# Peripherals.net
KiCad netlist of a schematic drawn in Altium Designer
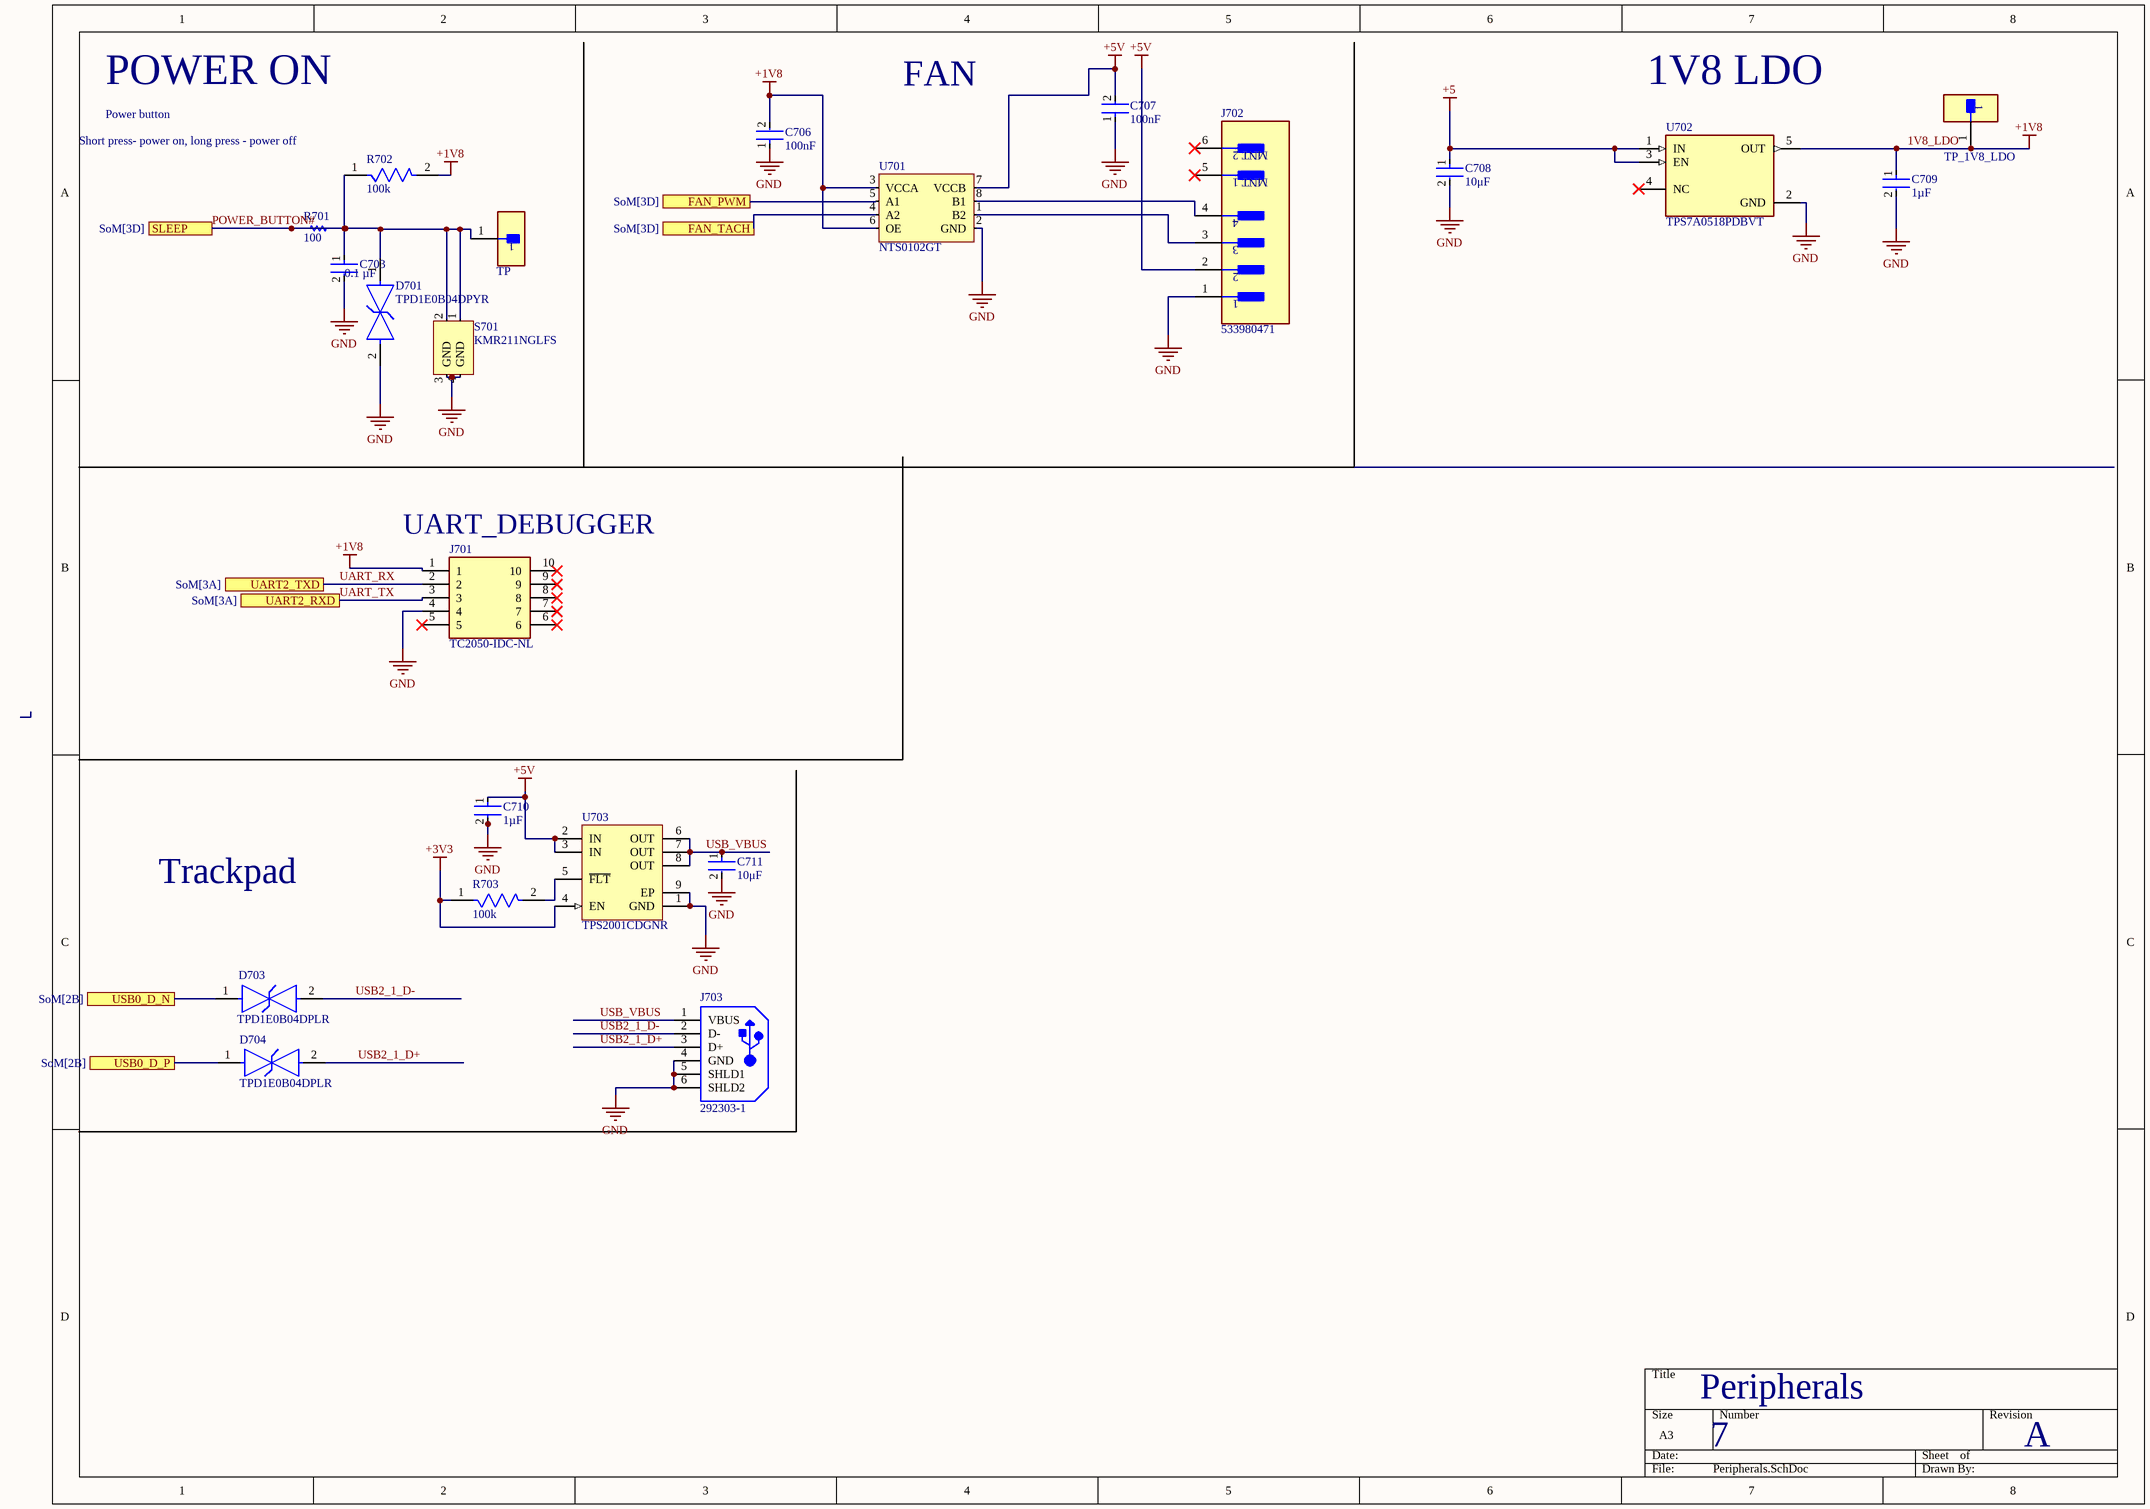
[diagram p0: Peripherals.SchDoc]

(export (version "E")
  (design (tool "Eeschema 10.0.6"))
  (components
    (comp (ref "C703")
      (value "0.1 µF")
      (footprint "FP-GRM155-0_05-IPC_B")
      (description "Chip Multilayer Ceramic Capacitors for General Purpose, 0402, 0.10uF, X7R, 15%, 10%, 50V")
      (fields (field (name "TOLERANCE") "10%"))
      (libsource (lib "Altium Content Vault") (part "02cd4be3c70576c341d710602a673aa"))
    )
    (comp (ref "C706")
      (value "100nF")
      (footprint "FP-GRM155-0_05-IPC_B")
      (description "Chip Multilayer Ceramic Capacitors for General Purpose, 0402, 0.10uF, X7R, 15%, 10%, 50V")
      (fields (field (name "VOLTAGE") "50V") (field (name "TOLERANCE") "10%"))
      (libsource (lib "Altium Content Vault") (part "02cd4be3c70576c341d710602a673aa"))
    )
    (comp (ref "C707")
      (value "100nF")
      (footprint "FP-GRM155-0_05-IPC_B")
      (description "Chip Multilayer Ceramic Capacitors for General Purpose, 0402, 0.10uF, X7R, 15%, 10%, 50V")
      (fields (field (name "VOLTAGE") "50V") (field (name "TOLERANCE") "10%"))
      (libsource (lib "Altium Content Vault") (part "02cd4be3c70576c341d710602a673aa"))
    )
    (comp (ref "C708")
      (value "10μF")
      (footprint "FP-GRM31C-0_2-e0_3_0_8-MFG")
      (description "Chip Multilayer Ceramic Capacitors for General Purpose, 1206, 10uF, X7R, 15%, 10%, 25V")
      (fields (field (name "TOLERANCE") "10%") (field (name "VOLTAGE") "25V"))
      (libsource (lib "Altium Content Vault") (part "02cd4be3c70576c341d710602a673aa"))
    )
    (comp (ref "C709")
      (value "1µF")
      (footprint "FP-GRM15-0_1-MFG")
      (description "CAP CER 1UF 10V X5R 0402")
      (fields
        (field (name "OCTOPART") "https://octopart.com/grm155r61a105ke15d-murata-197442")
        (field (name "MANUFACTURER PART NUMBER") "GRM155R61A105KE15D")
      )
      (libsource (lib "Altium Content Vault") (part "02cd4be3c70576c341d710602a673aa"))
    )
    (comp (ref "C710")
      (value "1µF")
      (footprint "FP-GRM15-0_1-MFG")
      (description "CAP CER 1UF 10V X5R 0402")
      (fields
        (field (name "OCTOPART") "https://octopart.com/grm155r61a105ke15d-murata-197442")
        (field (name "MANUFACTURER PART NUMBER") "GRM155R61A105KE15D")
      )
      (libsource (lib "Altium Content Vault") (part "02cd4be3c70576c341d710602a673aa"))
    )
    (comp (ref "C711")
      (value "10μF")
      (footprint "FP-GRM31C-0_2-e0_3_0_8-MFG")
      (description "Chip Multilayer Ceramic Capacitors for General Purpose, 1206, 10uF, X7R, 15%, 10%, 25V")
      (fields (field (name "TOLERANCE") "10%") (field (name "VOLTAGE") "25V"))
      (libsource (lib "Altium Content Vault") (part "02cd4be3c70576c341d710602a673aa"))
    )
    (comp (ref "D701")
      (value "TPD1E0B04DPYR")
      (footprint "FP-DPY0002A-MFG")
      (description "TVS DIODE 3.6V 19V 2X1SON")
      (libsource (lib "Altium Content Vault") (part "a36d0a7f8073cfe218e18526ba77789"))
    )
    (comp (ref "D703")
      (value "TPD1E0B04DPLR")
      (footprint "FP-DPL0002A-MFG")
      (description "TVS DIODE 3.6V 10.1V 2X2SON")
      (libsource (lib "Altium Content Vault") (part "a36d0a7f8073cfe218e18526ba77789"))
    )
    (comp (ref "D704")
      (value "TPD1E0B04DPLR")
      (footprint "FP-DPL0002A-MFG")
      (description "TVS DIODE 3.6V 10.1V 2X2SON")
      (libsource (lib "Altium Content Vault") (part "a36d0a7f8073cfe218e18526ba77789"))
    )
    (comp (ref "J701")
      (value "TC2050-IDC-NL")
      (footprint "TAG-CONNECT_TC2050-IDC-NL")
      (description "Adapter Cbl Plug Of Nails 10PIN")
      (libsource (lib "Evan") (part "TC2050-IDC-NL"))
    )
    (comp (ref "J702")
      (value "533980471")
      (footprint "FP-533980471-MFG")
      (description "CONN HEADER SMD 4POS 1.25MM")
      (fields
        (field (name "OCTOPART") "https://octopart.com/53398-0471-molex-655296")
        (field (name "MANUFACTURER") "Molex")
      )
      (libsource (lib "Altium Content Vault") (part "3b6f738a5616415d78381ad43816e4a"))
    )
    (comp (ref "J703")
      (value "292303-1")
      (footprint "TE-292303-1_V")
      (fields (field (name "MANUFACTURER") "TE Connectivity"))
      (libsource (lib "Altium Content Vault") (part "USB-4-2SHLD"))
    )
    (comp (ref "R701")
      (value "100")
      (footprint "RESC1005X40X25ML05T10")
      (fields (field (name "PART NUMBER") "RC0402FR-07100RL") (field (name "MANUFACTURER") "Yageo / Phycomp"))
      (libsource (lib "Altium Content Vault") (part "RES"))
    )
    (comp (ref "R702")
      (value "100k")
      (footprint "FP-RC0402-0_4-IPC_A")
      (description "RES 100K OHM 5% 1/16W 0402")
      (fields (field (name "TOLERANCE") "5%"))
      (libsource (lib "Altium Content Vault") (part "1029c3af85768c4190bb7ad29bc67b5"))
    )
    (comp (ref "R703")
      (value "100k")
      (footprint "FP-RC0402-0_4-IPC_A")
      (description "RES 100K OHM 5% 1/16W 0402")
      (fields (field (name "TOLERANCE") "5%"))
      (libsource (lib "Altium Content Vault") (part "1029c3af85768c4190bb7ad29bc67b5"))
    )
    (comp (ref "S701")
      (value "KMR211NGLFS")
      (footprint "SW_KMR211NGLFS")
      (description "Switch Tactile N.O. SPST Round Button Gull Wing 0.05A 32VDC 1VA 200000Cycle 1.2N SMD T/R")
      (libsource (lib "Evan") (part "KMR211NGLFS-Symbol-1"))
    )
    (comp (ref "TP700")
      (value "TP")
      (footprint "FP-S2751-46R-MFG")
      (description "PC TEST POINT NATURAL")
      (libsource (lib "") (part "dd45045ce8184df9e99e12baf3f412c_1"))
    )
    (comp (ref "TP701")
      (value "TP_1V8_LDO")
      (footprint "FP-S2751-46R-MFG")
      (description "PC TEST POINT NATURAL")
      (libsource (lib "Altium Content Vault") (part "dd45045ce8184df9e99e12baf3f412c"))
    )
    (comp (ref "U701")
      (value "NTS0102GT")
      (footprint "PSON50P100X195X50-8N")
      (description "Line Transceiver, PDSO8, 1 X 1.95 Mm, 0.50 Mm Height, Plastic, MO-252, SOT833-1, SON-8")
      (libsource (lib "Evan") (part "NTS0102GT-Symbol-1"))
    )
    (comp (ref "U702")
      (value "TPS7A0518PDBVT")
      (footprint "SOT95P280X145-5N")
      (description "200mA, ultra-low-IQ, high-accuracy, low-dropout voltage regulator with enable 5-SOT-23 -40 to 125")
      (libsource (lib "Evan") (part "TPS7A0518PDBVT"))
    )
    (comp (ref "U703")
      (value "TPS2001CDGNR")
      (footprint "DGN0008D_L")
      (fields (field (name "MANUFACTURER") "Texas Instruments"))
      (libsource (lib "Altium Content Vault") (part "TI-TPS2001CDGN8"))
    )
  )
  (nets
    (net (code "1") (name "+1V8") (class "Default")
      (node (ref "C706") (pin "2") (pinfunction "2_2") (pintype "passive"))
      (node (ref "C709") (pin "1") (pinfunction "1_1") (pintype "passive"))
      (node (ref "J701") (pin "1") (pinfunction "1_1") (pintype "passive"))
      (node (ref "R702") (pin "2") (pinfunction "2_2") (pintype "passive"))
      (node (ref "TP701") (pin "1") (pinfunction "1_1") (pintype "passive"))
      (node (ref "U701") (pin "3") (pinfunction "VCCA_3") (pintype "input"))
      (node (ref "U701") (pin "6") (pinfunction "OE_6") (pintype "input"))
      (node (ref "U702") (pin "5") (pinfunction "OUT_5") (pintype "output"))
    )
    (net (code "2") (name "+3V3") (class "Default")
      (node (ref "R703") (pin "1") (pinfunction "1_1") (pintype "passive"))
      (node (ref "U703") (pin "4") (pinfunction "EN_4") (pintype "input"))
    )
    (net (code "3") (name "+5") (class "Default")
      (node (ref "C708") (pin "1") (pinfunction "1_1") (pintype "passive"))
      (node (ref "U702") (pin "1") (pinfunction "IN_1") (pintype "input"))
      (node (ref "U702") (pin "3") (pinfunction "EN_3") (pintype "input"))
    )
    (net (code "4") (name "+5V") (class "Default")
      (node (ref "C707") (pin "2") (pinfunction "2_2") (pintype "passive"))
      (node (ref "C710") (pin "1") (pinfunction "1_1") (pintype "passive"))
      (node (ref "J702") (pin "2") (pinfunction "2_2") (pintype "passive"))
      (node (ref "U701") (pin "7") (pinfunction "VCCB_7") (pintype "input"))
      (node (ref "U703") (pin "2") (pinfunction "IN_2") (pintype "power_in"))
      (node (ref "U703") (pin "3") (pinfunction "IN_3") (pintype "power_in"))
    )
    (net (code "5") (name "/FAN_PWM") (class "Default")
      (node (ref "U701") (pin "5") (pinfunction "A1_5") (pintype "input"))
    )
    (net (code "6") (name "/FAN_TACH") (class "Default")
      (node (ref "U701") (pin "4") (pinfunction "A2_4") (pintype "output"))
    )
    (net (code "7") (name "/POWER_BUTTON#") (class "Default")
      (node (ref "C703") (pin "1") (pinfunction "1_1") (pintype "passive"))
      (node (ref "D701") (pin "1") (pinfunction "1_IO_1") (pintype "passive"))
      (node (ref "R701") (pin "1") (pinfunction "1_1") (pintype "passive"))
      (node (ref "R701") (pin "2") (pinfunction "2_2") (pintype "passive"))
      (node (ref "R702") (pin "1") (pinfunction "1_1") (pintype "passive"))
      (node (ref "S701") (pin "1") (pintype "input"))
      (node (ref "S701") (pin "2") (pintype "input"))
      (node (ref "TP700") (pin "1") (pinfunction "1_1") (pintype "passive"))
    )
    (net (code "8") (name "/UART_RX") (class "Default")
      (node (ref "J701") (pin "2") (pinfunction "2_2") (pintype "passive"))
    )
    (net (code "9") (name "/UART_TX") (class "Default")
      (node (ref "J701") (pin "3") (pinfunction "3_3") (pintype "passive"))
    )
    (net (code "10") (name "/USB0_D_N") (class "Default")
      (node (ref "D703") (pin "1") (pinfunction "1_IO_1") (pintype "passive"))
    )
    (net (code "11") (name "/USB0_D_P") (class "Default")
      (node (ref "D704") (pin "1") (pinfunction "1_IO_1") (pintype "passive"))
    )
    (net (code "12") (name "/USB2_1_D+") (class "Default")
      (node (ref "D704") (pin "2") (pinfunction "2_IO_2") (pintype "passive"))
      (node (ref "J703") (pin "3") (pinfunction "D+_3") (pintype "passive"))
    )
    (net (code "13") (name "/USB2_1_D-") (class "Default")
      (node (ref "D703") (pin "2") (pinfunction "2_IO_2") (pintype "passive"))
      (node (ref "J703") (pin "2") (pinfunction "D-_2") (pintype "passive"))
    )
    (net (code "14") (name "/USB_VBUS") (class "Default")
      (node (ref "C711") (pin "1") (pinfunction "1_1") (pintype "passive"))
      (node (ref "J703") (pin "1") (pinfunction "VBUS_1") (pintype "passive"))
      (node (ref "U703") (pin "6") (pinfunction "OUT_6") (pintype "power_in"))
      (node (ref "U703") (pin "7") (pinfunction "OUT_7") (pintype "power_in"))
      (node (ref "U703") (pin "8") (pinfunction "OUT_8") (pintype "power_in"))
    )
    (net (code "15") (name "GND") (class "Default")
      (node (ref "C703") (pin "2") (pinfunction "2_2") (pintype "passive"))
      (node (ref "C706") (pin "1") (pinfunction "1_1") (pintype "passive"))
      (node (ref "C707") (pin "1") (pinfunction "1_1") (pintype "passive"))
      (node (ref "C708") (pin "2") (pinfunction "2_2") (pintype "passive"))
      (node (ref "C709") (pin "2") (pinfunction "2_2") (pintype "passive"))
      (node (ref "C710") (pin "2") (pinfunction "2_2") (pintype "passive"))
      (node (ref "C711") (pin "2") (pinfunction "2_2") (pintype "passive"))
      (node (ref "D701") (pin "2") (pinfunction "2_IO_2") (pintype "passive"))
      (node (ref "J701") (pin "4") (pinfunction "4_4") (pintype "passive"))
      (node (ref "J702") (pin "1") (pinfunction "1_1") (pintype "passive"))
      (node (ref "J703") (pin "4") (pinfunction "GND_4") (pintype "passive"))
      (node (ref "J703") (pin "5") (pinfunction "SHLD1_5") (pintype "passive"))
      (node (ref "J703") (pin "6") (pinfunction "SHLD2_6") (pintype "passive"))
      (node (ref "S701") (pin "3") (pinfunction "GND_3") (pintype "input"))
      (node (ref "S701") (pin "4") (pinfunction "GND_4") (pintype "input"))
      (node (ref "U701") (pin "2") (pinfunction "GND_2") (pintype "input"))
      (node (ref "U702") (pin "2") (pinfunction "GND_2") (pintype "power_in"))
      (node (ref "U703") (pin "1") (pinfunction "GND_1") (pintype "power_in"))
      (node (ref "U703") (pin "9") (pinfunction "EP_9") (pintype "power_in"))
    )
    (net (code "16") (name "Net-(U701-B1)") (class "Default")
      (node (ref "J702") (pin "4") (pinfunction "4_4") (pintype "passive"))
      (node (ref "U701") (pin "8") (pinfunction "B1_8") (pintype "input"))
    )
    (net (code "17") (name "Net-(U701-B2)") (class "Default")
      (node (ref "J702") (pin "3") (pinfunction "3_3") (pintype "passive"))
      (node (ref "U701") (pin "1") (pinfunction "B2_1") (pintype "input"))
    )
    (net (code "18") (name "Net-(U703-~{FLT})") (class "Default")
      (node (ref "R703") (pin "2") (pinfunction "2_2") (pintype "passive"))
      (node (ref "U703") (pin "5") (pinfunction "~{FLT}_5") (pintype "tri_state"))
    )
    (net (code "19") (name "unconnected-(J701-Pad5)") (class "Default")
      (node (ref "J701") (pin "5") (pinfunction "5_5") (pintype "passive+no_connect"))
    )
    (net (code "20") (name "unconnected-(J701-Pad6)") (class "Default")
      (node (ref "J701") (pin "6") (pinfunction "6_6") (pintype "passive+no_connect"))
    )
    (net (code "21") (name "unconnected-(J701-Pad7)") (class "Default")
      (node (ref "J701") (pin "7") (pinfunction "7_7") (pintype "passive+no_connect"))
    )
    (net (code "22") (name "unconnected-(J701-Pad8)") (class "Default")
      (node (ref "J701") (pin "8") (pinfunction "8_8") (pintype "passive+no_connect"))
    )
    (net (code "23") (name "unconnected-(J701-Pad9)") (class "Default")
      (node (ref "J701") (pin "9") (pinfunction "9_9") (pintype "passive+no_connect"))
    )
    (net (code "24") (name "unconnected-(J701-Pad10)") (class "Default")
      (node (ref "J701") (pin "10") (pinfunction "10_10") (pintype "passive+no_connect"))
    )
    (net (code "25") (name "unconnected-(J702-MNT_1-Pad5)") (class "Default")
      (node (ref "J702") (pin "5") (pinfunction "MNT_1_5") (pintype "passive+no_connect"))
    )
    (net (code "26") (name "unconnected-(J702-MNT_2-Pad6)") (class "Default")
      (node (ref "J702") (pin "6") (pinfunction "MNT_2_6") (pintype "passive+no_connect"))
    )
    (net (code "27") (name "unconnected-(U702-NC-Pad4)") (class "Default")
      (node (ref "U702") (pin "4") (pinfunction "NC_4") (pintype "passive+no_connect"))
    )
  )
)
